# TGE_NEIL_v1.net
KiCad netlist of a schematic drawn in EAGLE
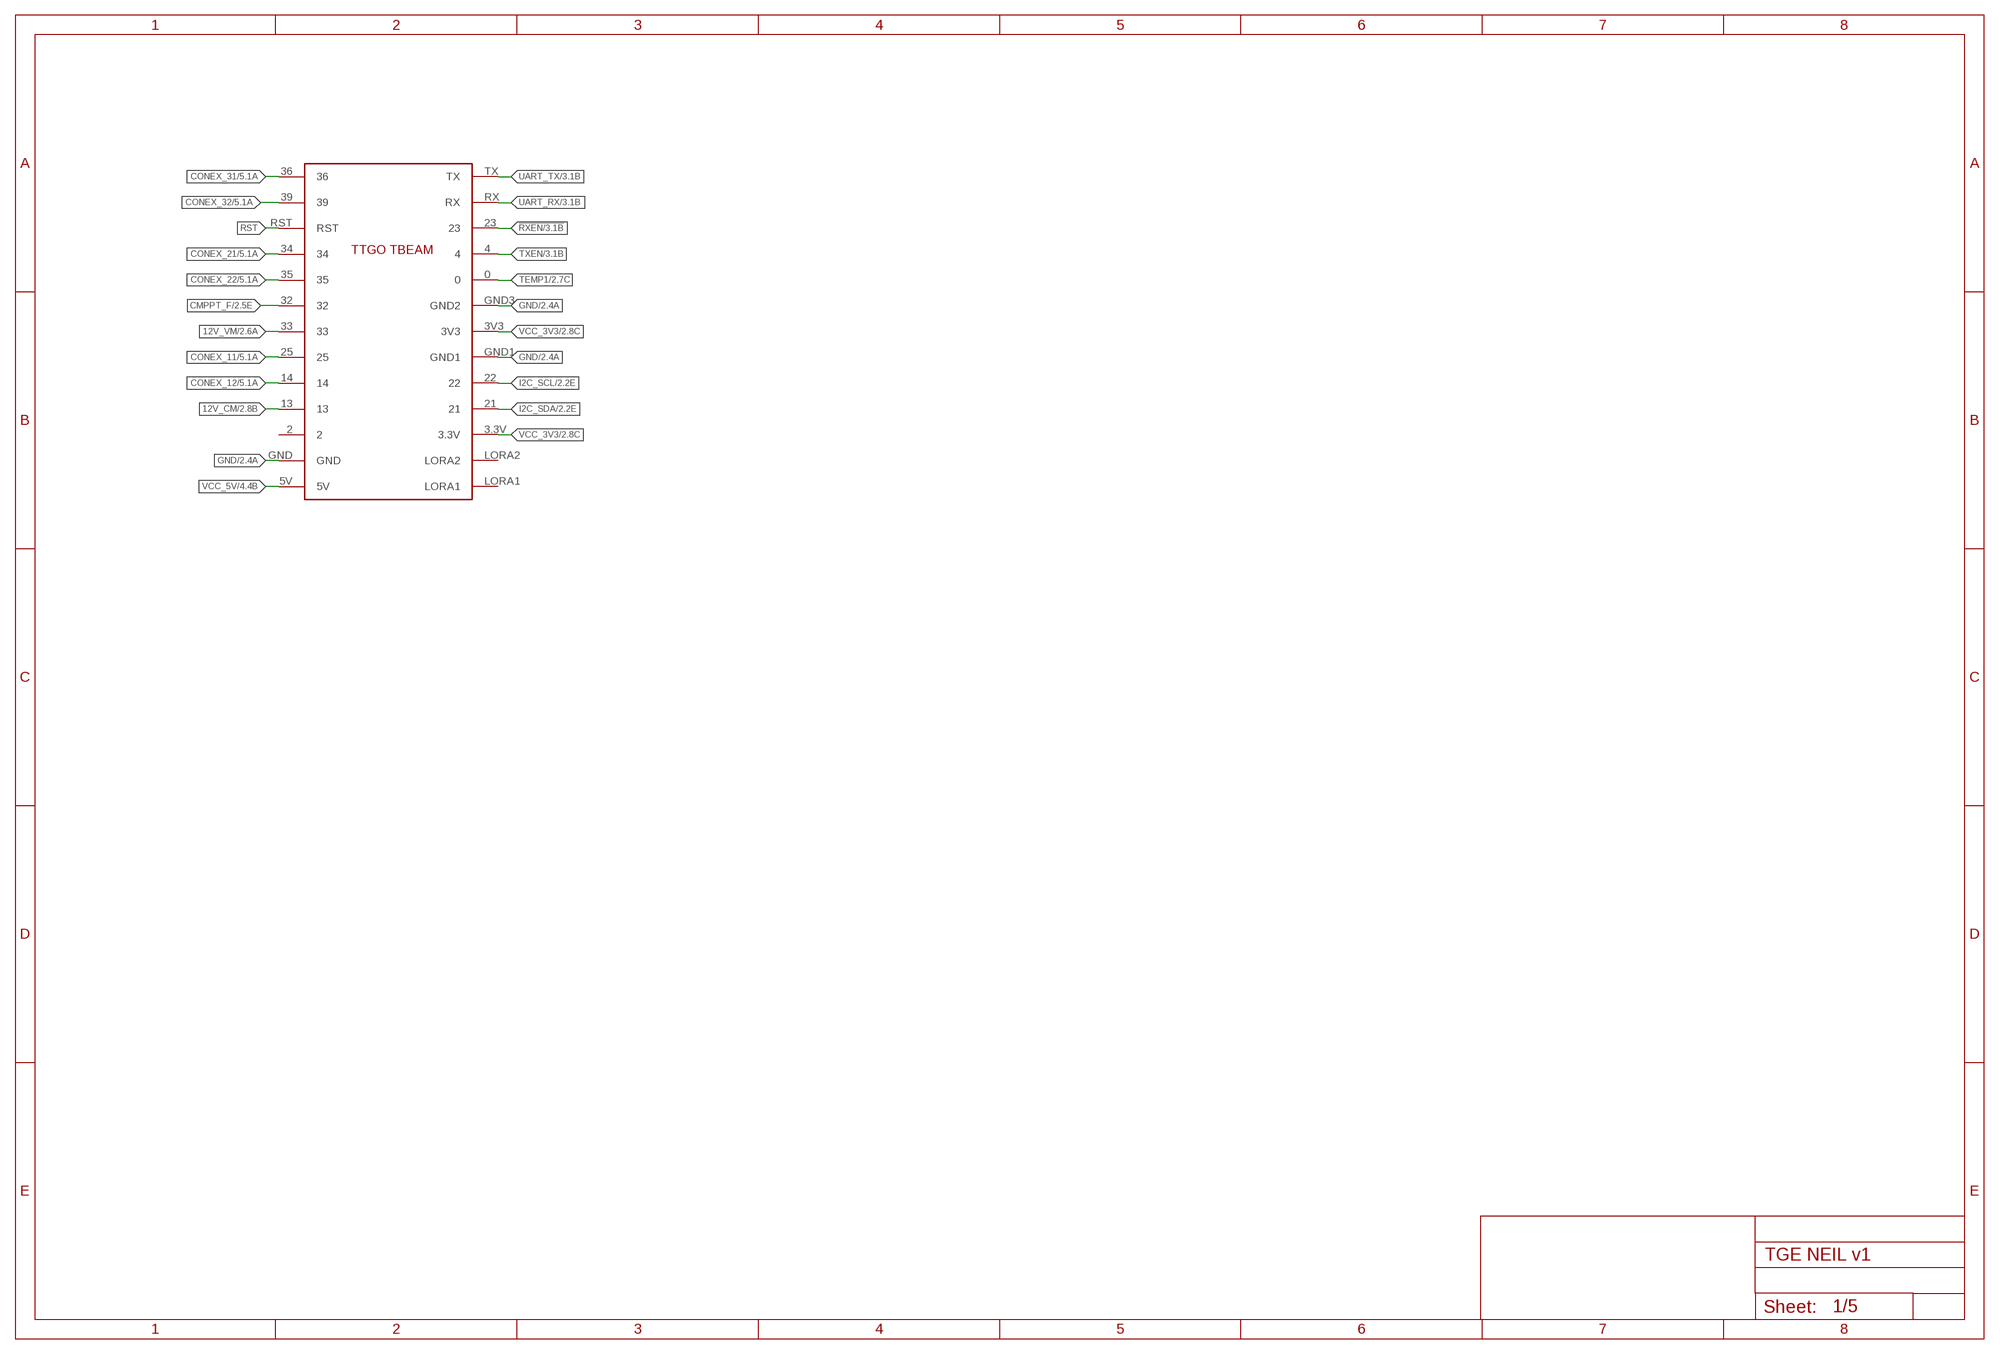
[diagram p0: schematic, sheet 1]
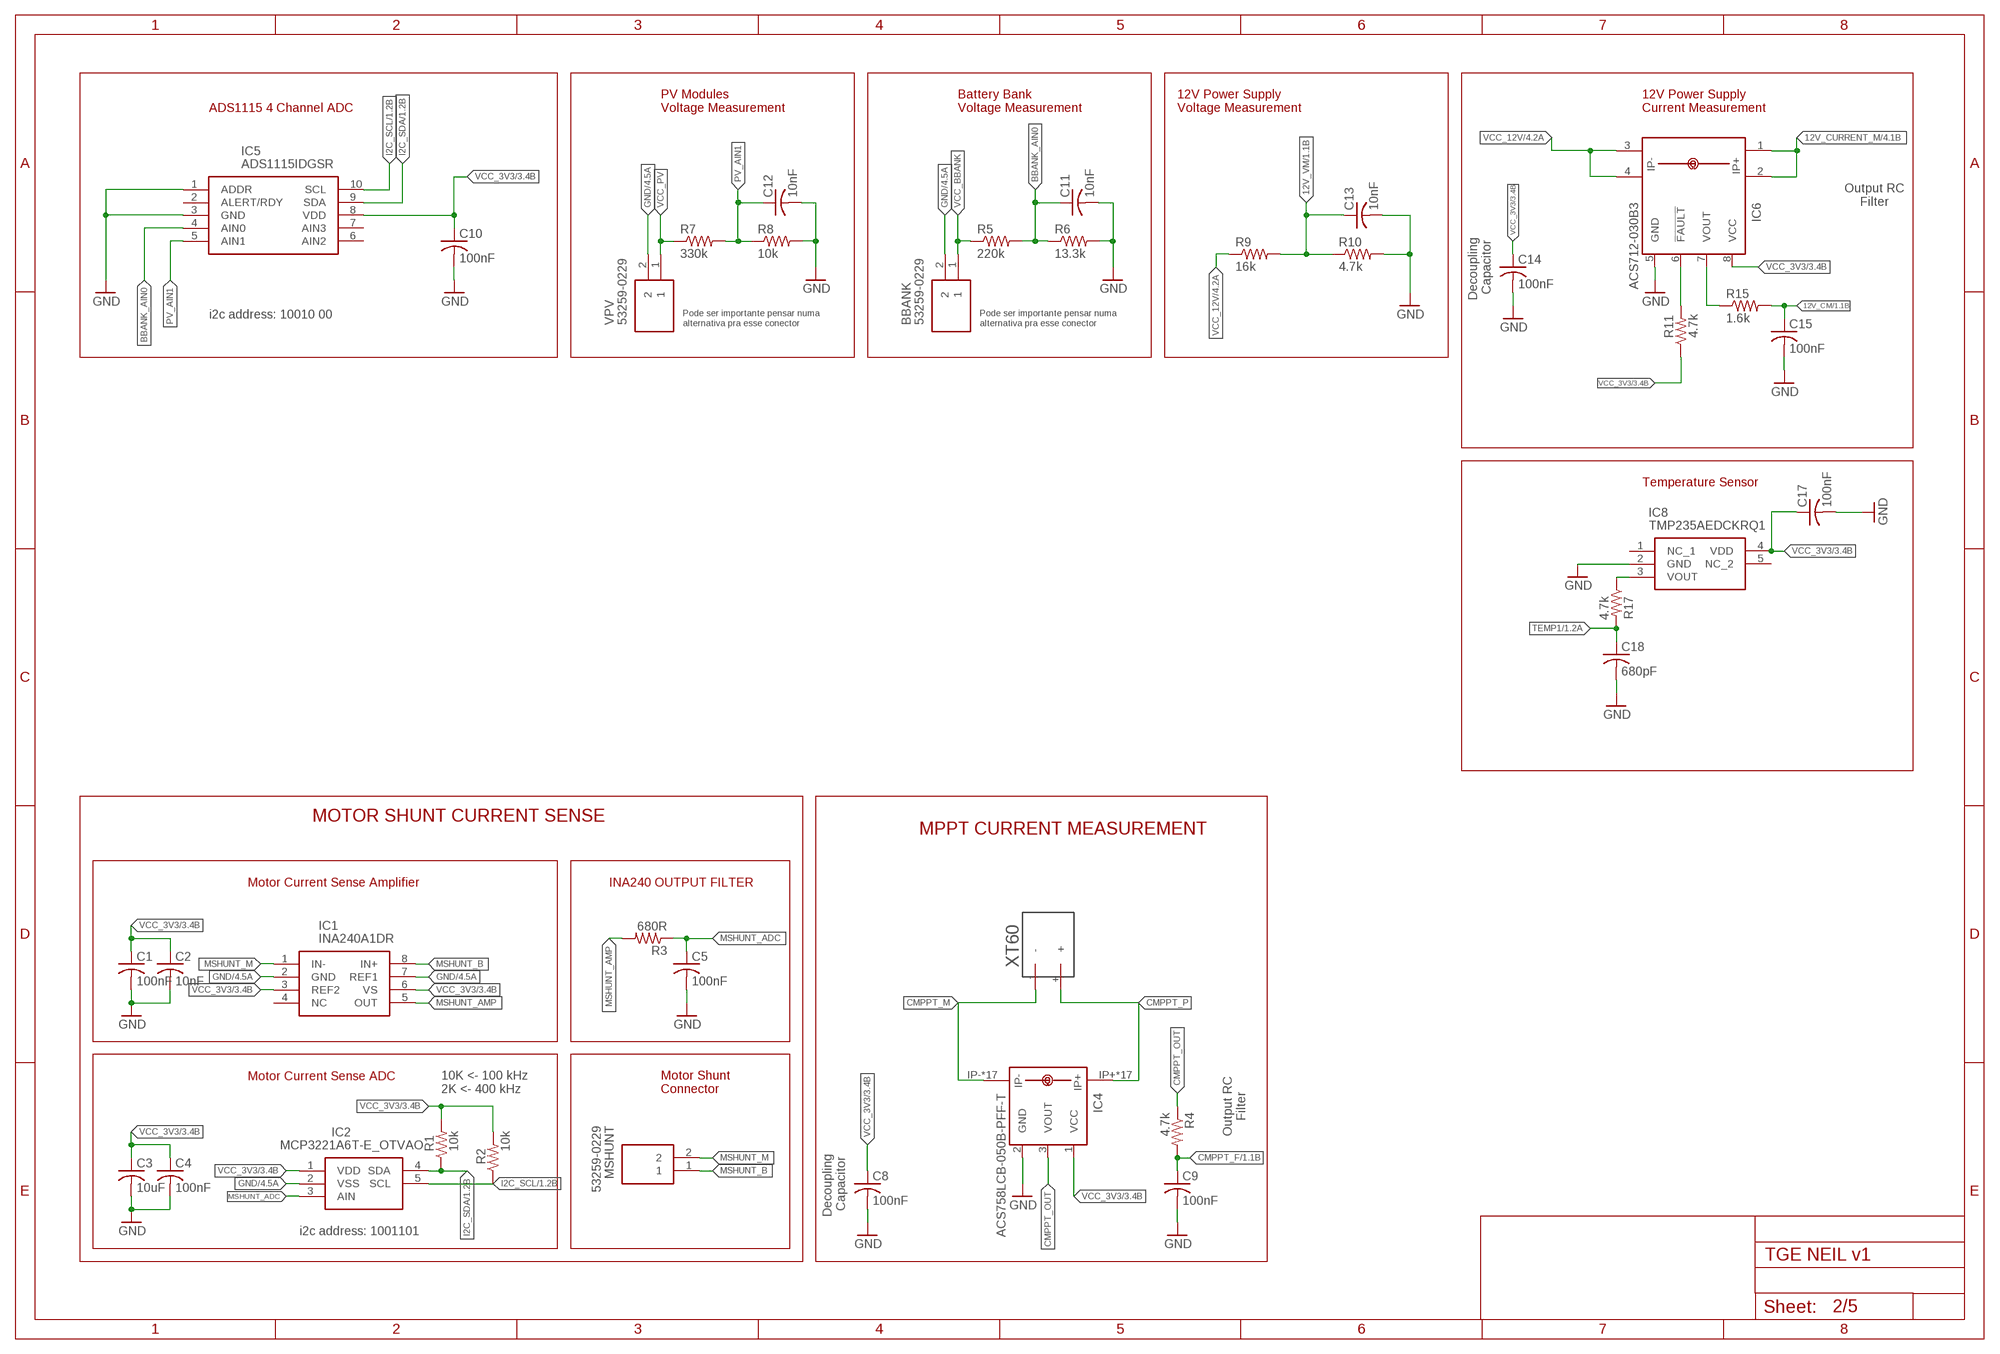
[diagram p1: schematic, sheet 2]
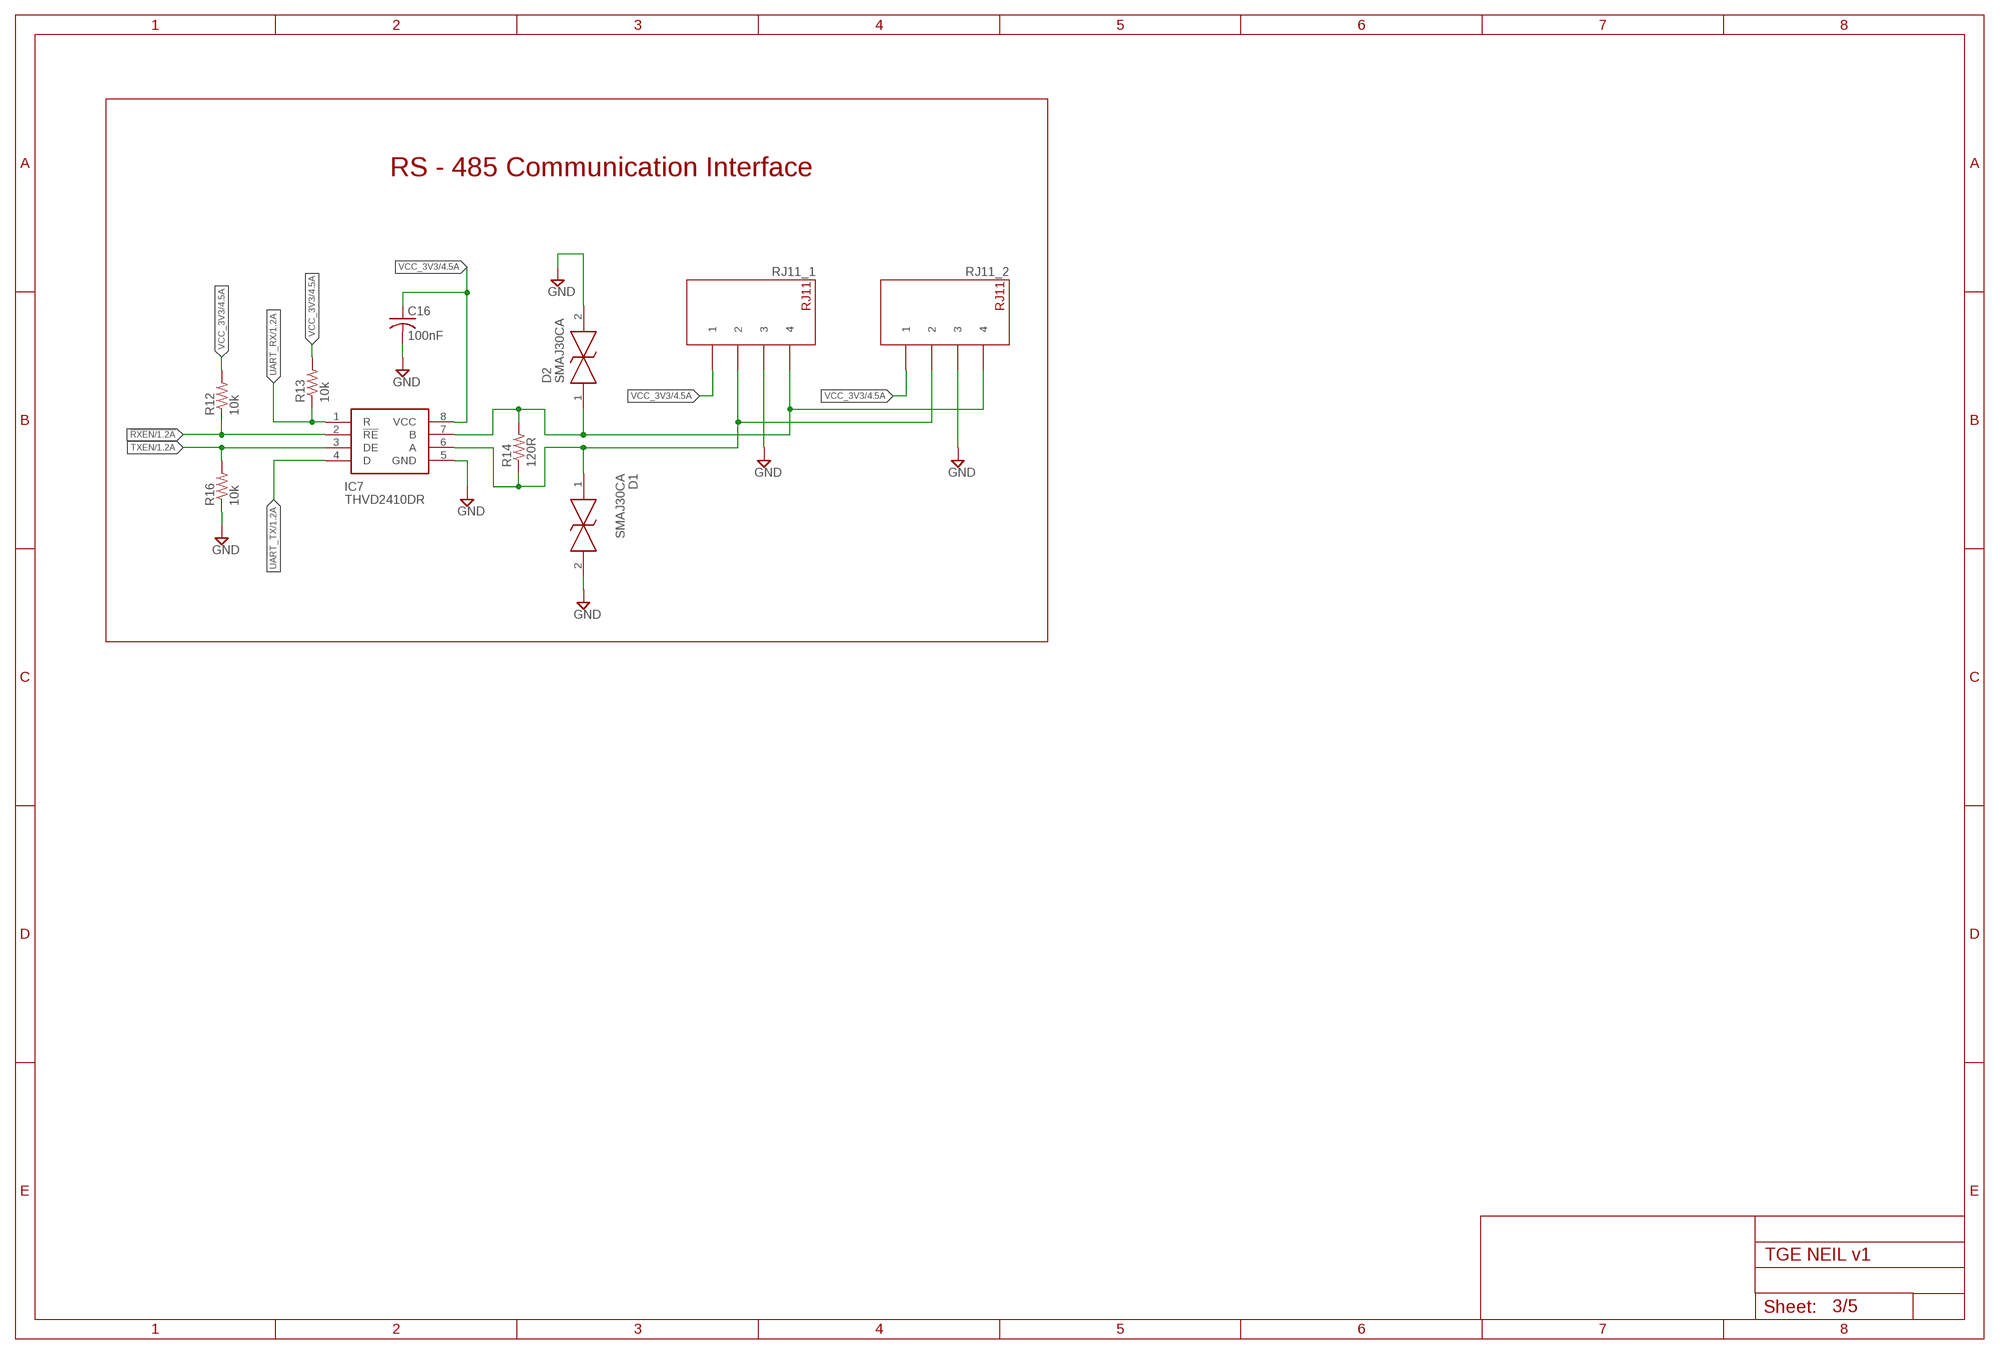
[diagram p2: schematic, sheet 3]
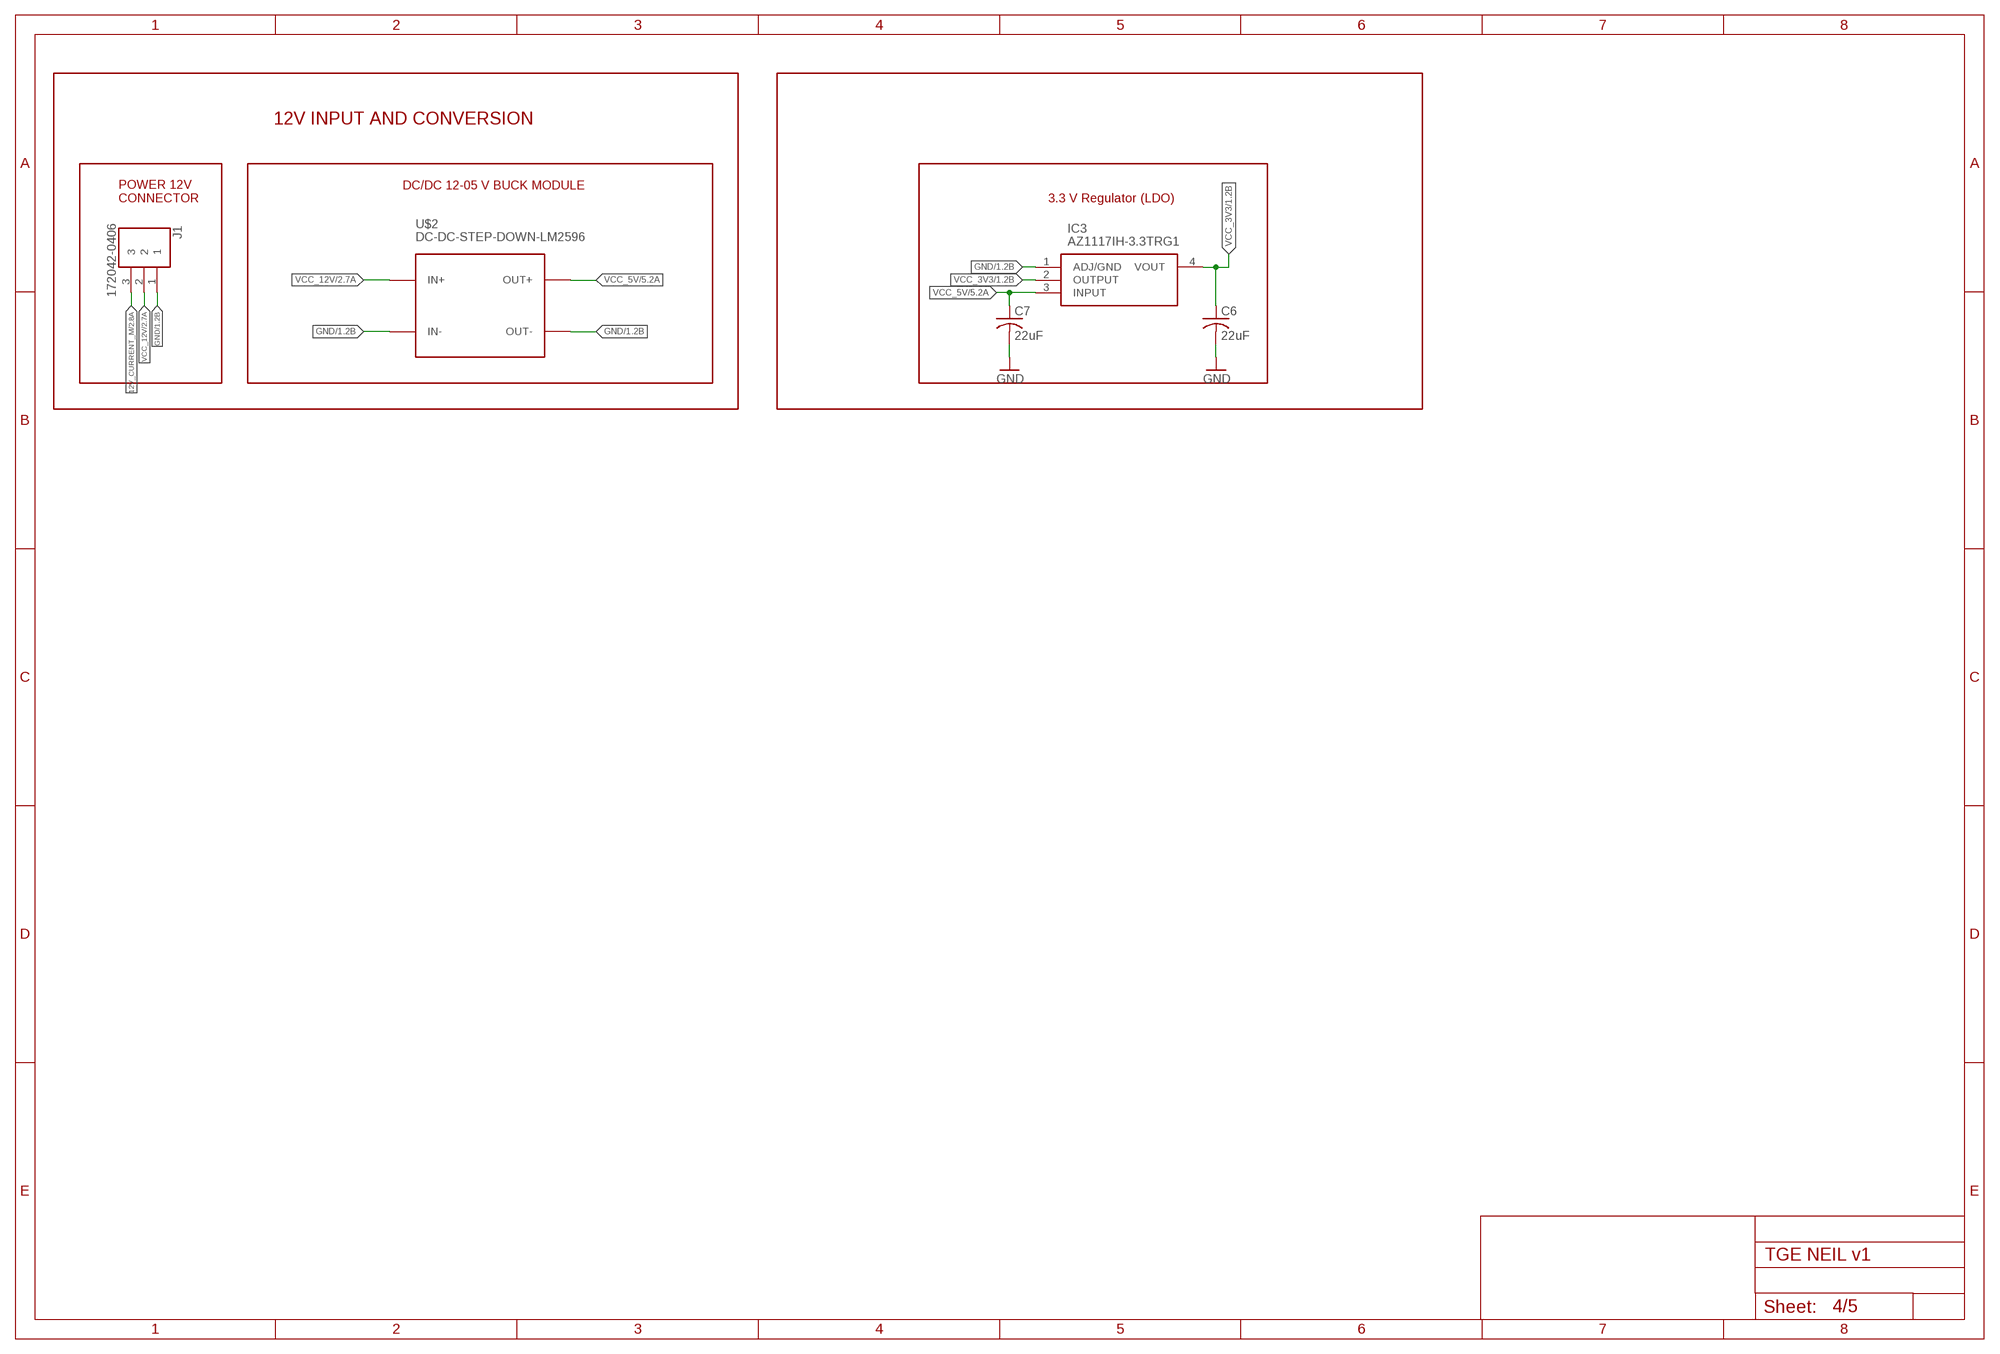
[diagram p3: schematic, sheet 4]
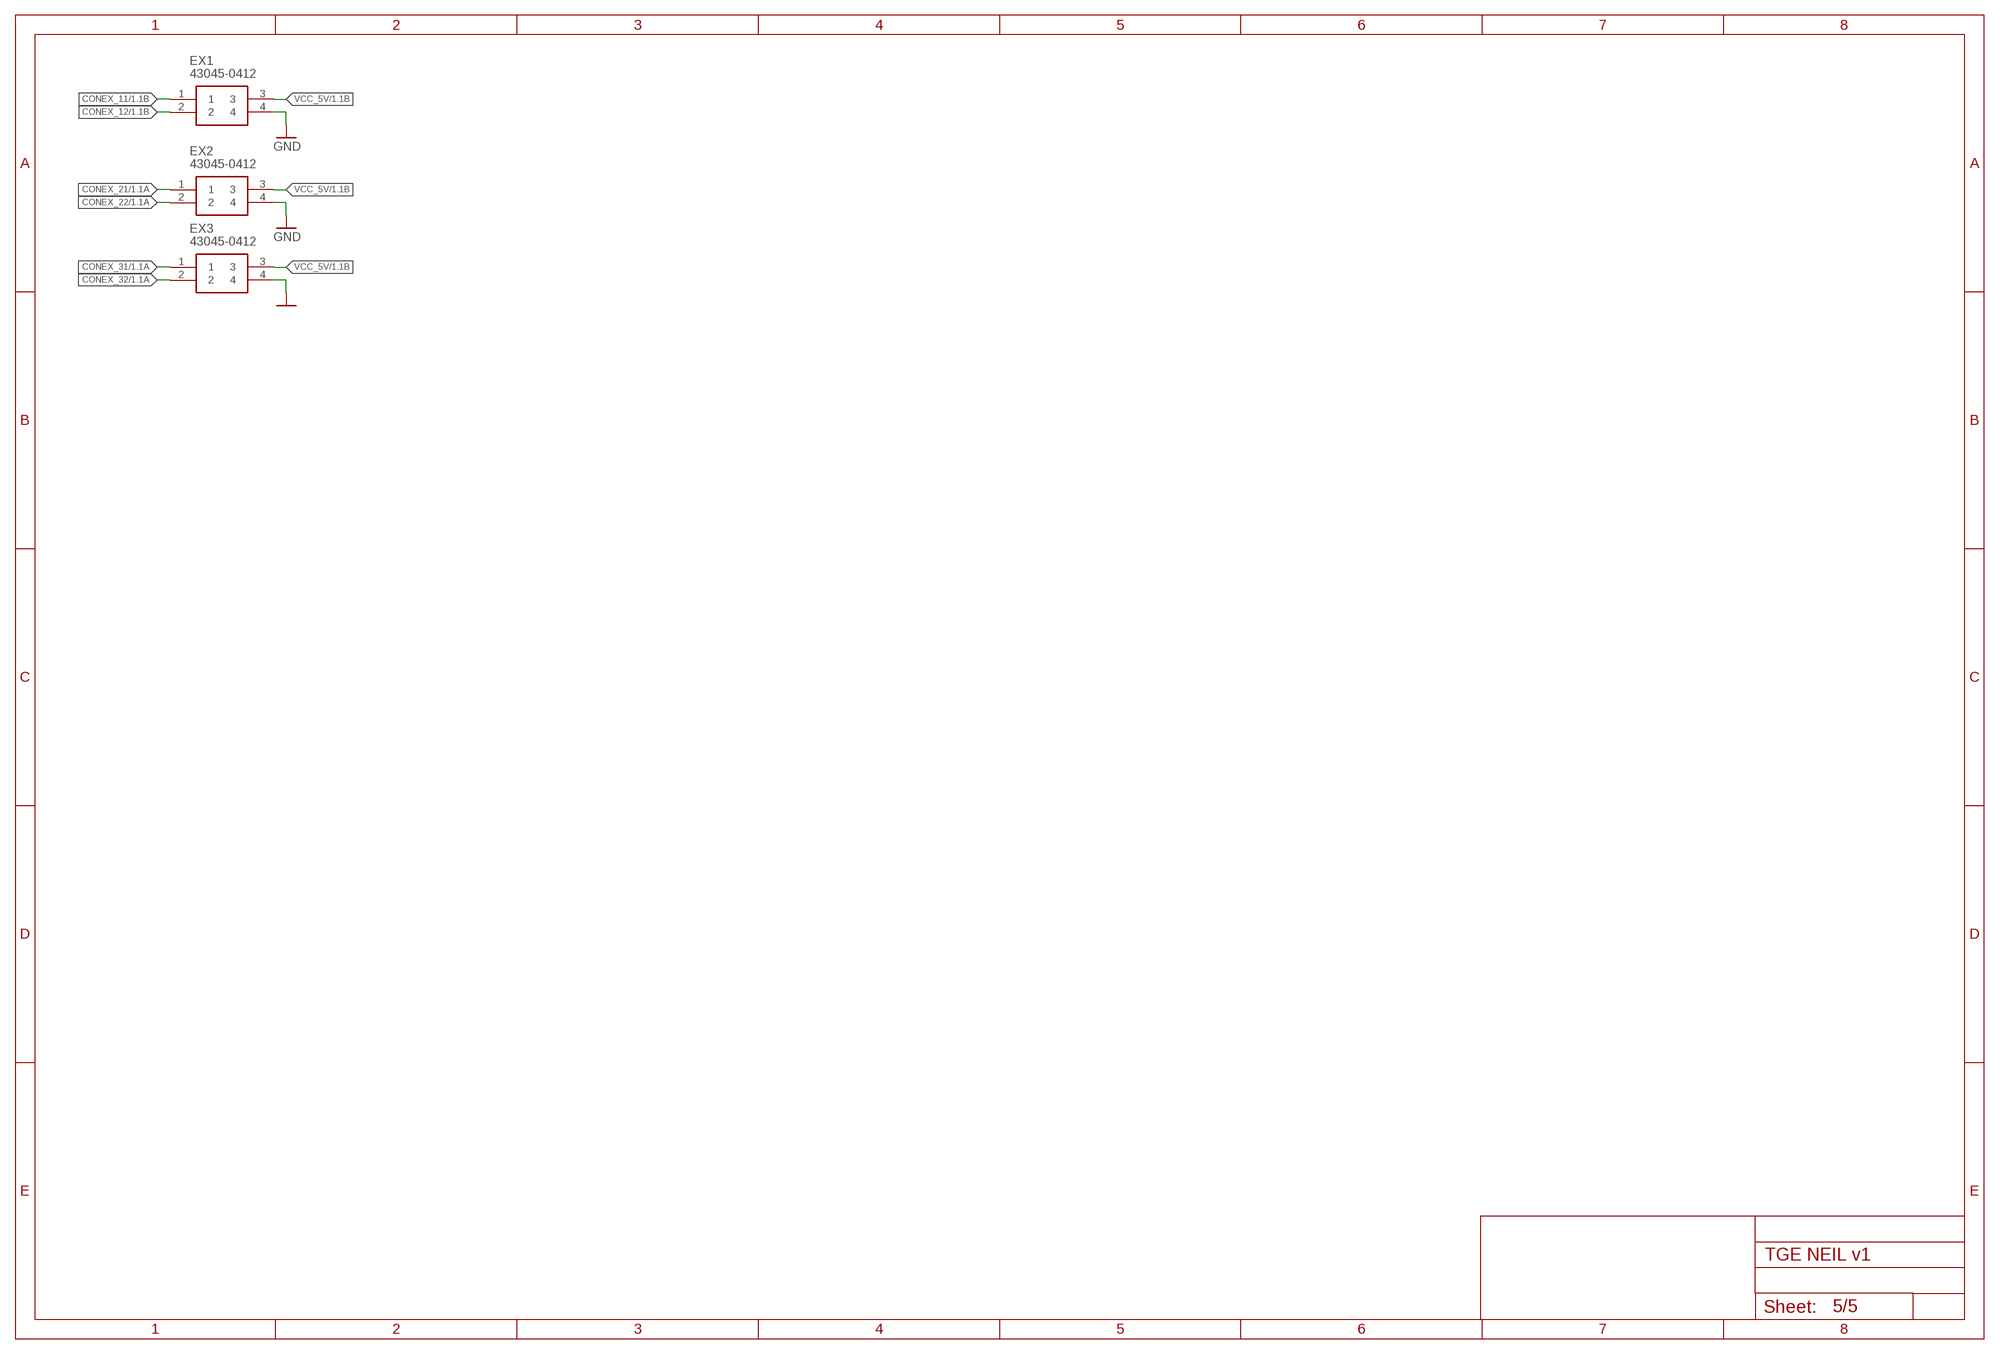
[diagram p4: schematic, sheet 5]

(export (version "E")
  (design (tool "Eeschema 10.0.6"))
  (components
    (comp (ref "BBANK")
      (value "53259-0229")
      (footprint "eagle-import:0532590229")
      (fields (field (name "MOUSER_PART_NUMBER") "538-53259-0229"))
      (libsource (lib "eagle-import") (part "53259-0229"))
    )
    (comp (ref "C1")
      (value "100nF")
      (footprint "eagle-import:C0805")
      (libsource (lib "eagle-import") (part "C-USC0805"))
    )
    (comp (ref "C2")
      (value "10nF")
      (footprint "eagle-import:C0805")
      (libsource (lib "eagle-import") (part "C-USC0805"))
    )
    (comp (ref "C3")
      (value "10uF")
      (footprint "eagle-import:C0805")
      (libsource (lib "eagle-import") (part "C-USC0805"))
    )
    (comp (ref "C4")
      (value "100nF")
      (footprint "eagle-import:C0805")
      (libsource (lib "eagle-import") (part "C-USC0805"))
    )
    (comp (ref "C5")
      (value "100nF")
      (footprint "eagle-import:C0805")
      (libsource (lib "eagle-import") (part "C-USC0805"))
    )
    (comp (ref "C8")
      (value "100nF")
      (footprint "eagle-import:C0805")
      (libsource (lib "eagle-import") (part "C-USC0805"))
    )
    (comp (ref "C9")
      (value "100nF")
      (footprint "eagle-import:C0805")
      (libsource (lib "eagle-import") (part "C-USC0805"))
    )
    (comp (ref "C10")
      (value "100nF")
      (footprint "eagle-import:C0805")
      (libsource (lib "eagle-import") (part "C-USC0805"))
    )
    (comp (ref "C11")
      (value "10nF")
      (footprint "eagle-import:C0805")
      (libsource (lib "eagle-import") (part "C-USC0805"))
    )
    (comp (ref "C12")
      (value "10nF")
      (footprint "eagle-import:C0805")
      (libsource (lib "eagle-import") (part "C-USC0805"))
    )
    (comp (ref "C13")
      (value "10nF")
      (footprint "eagle-import:C0805")
      (libsource (lib "eagle-import") (part "C-USC0805"))
    )
    (comp (ref "C14")
      (value "100nF")
      (footprint "eagle-import:C0805")
      (libsource (lib "eagle-import") (part "C-USC0805"))
    )
    (comp (ref "C15")
      (value "100nF")
      (footprint "eagle-import:C0805")
      (libsource (lib "eagle-import") (part "C-USC0805"))
    )
    (comp (ref "C17")
      (value "100nF")
      (footprint "eagle-import:C0805")
      (libsource (lib "eagle-import") (part "C-USC0805"))
    )
    (comp (ref "C18")
      (value "680pF")
      (footprint "eagle-import:C0805")
      (libsource (lib "eagle-import") (part "C-USC0805"))
    )
    (comp (ref "IC1")
      (value "INA240A1DR")
      (footprint "eagle-import:SOIC127P600X175-8N")
      (fields (field (name "MOUSER_PART_NUMBER") "595-INA240A1DR"))
      (libsource (lib "eagle-import") (part "INA240A1DR"))
    )
    (comp (ref "IC2")
      (value "MCP3221A6T-E_OTVAO")
      (footprint "eagle-import:SOT95P280X145-5N")
      (fields
        (field (name "MANUFACTURER_PART_NUMBER") "MCP3221A6T-E/OTVAO")
        (field (name "MOUSER_PART_NUMBER") "579-MCP3221A6TEOTVAO")
      )
      (libsource (lib "eagle-import") (part "MCP3221A6T-E_OTVAO"))
    )
    (comp (ref "IC4")
      (value "ACS758LCB-050B-PFF-T")
      (footprint "eagle-import:CB-PFF")
      (libsource (lib "eagle-import") (part "ACS758LCB-050B-PFF-T"))
    )
    (comp (ref "IC5")
      (value "ADS1115IDGSR")
      (footprint "eagle-import:SOP50P490X110-10N")
      (fields (field (name "MOUSER_PART_NUMBER") "595-ADS1115IDGSR"))
      (libsource (lib "eagle-import") (part "ADS1115IDGSR"))
    )
    (comp (ref "IC6")
      (value "ACS712-030B3")
      (footprint "eagle-import:SOIC8")
      (libsource (lib "eagle-import") (part "ACS712-LC"))
    )
    (comp (ref "IC8")
      (value "TMP235AEDCKRQ1")
      (footprint "eagle-import:SOT65P210X110-5N")
      (fields (field (name "MOUSER_PART_NUMBER") "595-TMP235AEDCKRQ1"))
      (libsource (lib "eagle-import") (part "TMP235AEDCKRQ1"))
    )
    (comp (ref "MSHUNT")
      (value "53259-0229")
      (footprint "eagle-import:0532590229")
      (fields (field (name "MOUSER_PART_NUMBER") "538-53259-0229"))
      (libsource (lib "eagle-import") (part "53259-0229"))
    )
    (comp (ref "R1")
      (value "10k")
      (footprint "eagle-import:R0805")
      (libsource (lib "eagle-import") (part "R-US_R0805"))
    )
    (comp (ref "R2")
      (value "10k")
      (footprint "eagle-import:R0805")
      (libsource (lib "eagle-import") (part "R-US_R0805"))
    )
    (comp (ref "R3")
      (value "680R")
      (footprint "eagle-import:R0805")
      (libsource (lib "eagle-import") (part "R-US_R0805"))
    )
    (comp (ref "R4")
      (value "4.7k")
      (footprint "eagle-import:R0805")
      (libsource (lib "eagle-import") (part "R-US_R0805"))
    )
    (comp (ref "R5")
      (value "220k")
      (footprint "eagle-import:R0805")
      (libsource (lib "eagle-import") (part "R-US_R0805"))
    )
    (comp (ref "R6")
      (value "13.3k")
      (footprint "eagle-import:R0805")
      (libsource (lib "eagle-import") (part "R-US_R0805"))
    )
    (comp (ref "R7")
      (value "330k")
      (footprint "eagle-import:R0805")
      (libsource (lib "eagle-import") (part "R-US_R0805"))
    )
    (comp (ref "R8")
      (value "10k")
      (footprint "eagle-import:R0805")
      (libsource (lib "eagle-import") (part "R-US_R0805"))
    )
    (comp (ref "R9")
      (value "16k")
      (footprint "eagle-import:R0805")
      (libsource (lib "eagle-import") (part "R-US_R0805"))
    )
    (comp (ref "R10")
      (value "4.7k")
      (footprint "eagle-import:R0805")
      (libsource (lib "eagle-import") (part "R-US_R0805"))
    )
    (comp (ref "R11")
      (value "4.7k")
      (footprint "eagle-import:R0805")
      (libsource (lib "eagle-import") (part "R-US_R0805"))
    )
    (comp (ref "R15")
      (value "1.6k")
      (footprint "eagle-import:R0805")
      (libsource (lib "eagle-import") (part "R-US_R0805"))
    )
    (comp (ref "R17")
      (value "4.7k")
      (footprint "eagle-import:R0805")
      (libsource (lib "eagle-import") (part "R-US_R0805"))
    )
    (comp (ref "U$3")
      (value "XT60")
      (footprint "eagle-import:XT60")
      (libsource (lib "eagle-import") (part "XT60"))
    )
    (comp (ref "VPV")
      (value "53259-0229")
      (footprint "eagle-import:0532590229")
      (fields (field (name "MOUSER_PART_NUMBER") "538-53259-0229"))
      (libsource (lib "eagle-import") (part "53259-0229"))
    )
    (comp (ref "EX1")
      (value "43045-0412")
      (footprint "eagle-import:43045-0412")
      (fields (field (name "MOUSER_PART_NUMBER") "538-43045-0412"))
      (libsource (lib "eagle-import") (part "43045-0412"))
    )
    (comp (ref "EX2")
      (value "43045-0412")
      (footprint "eagle-import:43045-0412")
      (fields (field (name "MOUSER_PART_NUMBER") "538-43045-0412"))
      (libsource (lib "eagle-import") (part "43045-0412"))
    )
    (comp (ref "EX3")
      (value "43045-0412")
      (footprint "eagle-import:43045-0412")
      (fields (field (name "MOUSER_PART_NUMBER") "538-43045-0412"))
      (libsource (lib "eagle-import") (part "43045-0412"))
    )
    (comp (ref "U$1")
      (value "TTGOBEAM")
      (footprint "eagle-import:TTGOBEAM")
      (libsource (lib "eagle-import") (part "TTGOBEAM"))
    )
    (comp (ref "C6")
      (value "22uF")
      (footprint "eagle-import:C0805")
      (libsource (lib "eagle-import") (part "C-USC0805"))
    )
    (comp (ref "C7")
      (value "22uF")
      (footprint "eagle-import:C0805")
      (libsource (lib "eagle-import") (part "C-USC0805"))
    )
    (comp (ref "IC3")
      (value "AZ1117IH-3.3TRG1")
      (footprint "eagle-import:SOT230P700X170-4N")
      (fields (field (name "MOUSER_PART_NUMBER") "621-AZ1117IH-3.3TRG1"))
      (libsource (lib "eagle-import") (part "AZ1117IH-3.3TRG1"))
    )
    (comp (ref "J1")
      (value "172042-0406")
      (footprint "eagle-import:MOLEX_172042-0406")
      (fields (field (name "MF") "Molex") (field (name "MP") "172042-0302"))
      (libsource (lib "eagle-import") (part "172042-0406"))
    )
    (comp (ref "U$2")
      (value "DC-DC-STEP-DOWN-LM2596")
      (footprint "eagle-import:DC-DC-STEP-DOWN-LM2596")
      (libsource (lib "eagle-import") (part "DC-DC-STEP-DOWN-LM2596"))
    )
    (comp (ref "C16")
      (value "100nF")
      (footprint "eagle-import:C0805")
      (libsource (lib "eagle-import") (part "C-USC0805"))
    )
    (comp (ref "D1")
      (value "SMAJ30CA")
      (footprint "eagle-import:DIONM5026X229N")
      (fields (field (name "MOUSER_PART_NUMBER") "576-SMAJ30CA"))
      (libsource (lib "eagle-import") (part "SMAJ30CA"))
    )
    (comp (ref "D2")
      (value "SMAJ30CA")
      (footprint "eagle-import:DIONM5026X229N")
      (fields (field (name "MOUSER_PART_NUMBER") "576-SMAJ30CA"))
      (libsource (lib "eagle-import") (part "SMAJ30CA"))
    )
    (comp (ref "IC7")
      (value "THVD2410DR")
      (footprint "eagle-import:SOIC127P600X175-8N")
      (fields (field (name "MOUSER_PART_NUMBER") "595-THVD2410DR"))
      (libsource (lib "eagle-import") (part "THVD2410DR"))
    )
    (comp (ref "R12")
      (value "10k")
      (footprint "eagle-import:M0805")
      (libsource (lib "eagle-import") (part "R-US_M0805"))
    )
    (comp (ref "R13")
      (value "10k")
      (footprint "eagle-import:M0805")
      (libsource (lib "eagle-import") (part "R-US_M0805"))
    )
    (comp (ref "R14")
      (value "120R")
      (footprint "eagle-import:M0805")
      (libsource (lib "eagle-import") (part "R-US_M0805"))
    )
    (comp (ref "R16")
      (value "10k")
      (footprint "eagle-import:M0805")
      (libsource (lib "eagle-import") (part "R-US_M0805"))
    )
    (comp (ref "RJ11_1")
      (value "TFC44")
      (footprint "eagle-import:TFC44")
      (libsource (lib "eagle-import") (part "TFC44"))
    )
    (comp (ref "RJ11_2")
      (value "TFC44")
      (footprint "eagle-import:TFC44")
      (libsource (lib "eagle-import") (part "TFC44"))
    )
  )
  (nets
    (net (code "1") (name "12V_CM") (class "Default")
      (node (ref "C15") (pin "1") (pinfunction "1_1") (pintype "passive"))
      (node (ref "R15") (pin "2") (pinfunction "2_2") (pintype "passive"))
      (node (ref "U$1") (pin "13") (pinfunction "13_13") (pintype "bidirectional"))
    )
    (net (code "2") (name "12V_CURRENT_M") (class "Default")
      (node (ref "IC6") (pin "1") (pinfunction "IP+_1") (pintype "passive"))
      (node (ref "IC6") (pin "2") (pinfunction "IP+1_2") (pintype "passive"))
      (node (ref "J1") (pin "3") (pinfunction "3_3") (pintype "passive"))
    )
    (net (code "3") (name "12V_VM") (class "Default")
      (node (ref "C13") (pin "1") (pinfunction "1_1") (pintype "passive"))
      (node (ref "R10") (pin "1") (pinfunction "1_1") (pintype "passive"))
      (node (ref "R9") (pin "2") (pinfunction "2_2") (pintype "passive"))
      (node (ref "U$1") (pin "33") (pinfunction "33_33") (pintype "bidirectional"))
    )
    (net (code "4") (name "BBANK_AIN0") (class "Default")
      (node (ref "C11") (pin "1") (pinfunction "1_1") (pintype "passive"))
      (node (ref "IC5") (pin "4") (pinfunction "AIN0_4") (pintype "bidirectional"))
      (node (ref "R5") (pin "2") (pinfunction "2_2") (pintype "passive"))
      (node (ref "R6") (pin "1") (pinfunction "1_1") (pintype "passive"))
    )
    (net (code "5") (name "CMPPT_F") (class "Default")
      (node (ref "C9") (pin "1") (pinfunction "1_1") (pintype "passive"))
      (node (ref "R4") (pin "2") (pinfunction "2_2") (pintype "passive"))
      (node (ref "U$1") (pin "32") (pinfunction "32_32") (pintype "bidirectional"))
    )
    (net (code "6") (name "CMPPT_M") (class "Default")
      (node (ref "IC4") (pin "IP-") (pinfunction "IP-_IP-") (pintype "passive"))
      (node (ref "IC4") (pin "IP-@10") (pinfunction "IP-_IP-@10") (pintype "passive"))
      (node (ref "IC4") (pin "IP-@11") (pinfunction "IP-_IP-@11") (pintype "passive"))
      (node (ref "IC4") (pin "IP-@12") (pinfunction "IP-_IP-@12") (pintype "passive"))
      (node (ref "IC4") (pin "IP-@13") (pinfunction "IP-_IP-@13") (pintype "passive"))
      (node (ref "IC4") (pin "IP-@14") (pinfunction "IP-_IP-@14") (pintype "passive"))
      (node (ref "IC4") (pin "IP-@15") (pinfunction "IP-_IP-@15") (pintype "passive"))
      (node (ref "IC4") (pin "IP-@16") (pinfunction "IP-_IP-@16") (pintype "passive"))
      (node (ref "IC4") (pin "IP-@17") (pinfunction "IP-_IP-@17") (pintype "passive"))
      (node (ref "IC4") (pin "IP-@2") (pinfunction "IP-_IP-@2") (pintype "passive"))
      (node (ref "IC4") (pin "IP-@3") (pinfunction "IP-_IP-@3") (pintype "passive"))
      (node (ref "IC4") (pin "IP-@4") (pinfunction "IP-_IP-@4") (pintype "passive"))
      (node (ref "IC4") (pin "IP-@5") (pinfunction "IP-_IP-@5") (pintype "passive"))
      (node (ref "IC4") (pin "IP-@6") (pinfunction "IP-_IP-@6") (pintype "passive"))
      (node (ref "IC4") (pin "IP-@7") (pinfunction "IP-_IP-@7") (pintype "passive"))
      (node (ref "IC4") (pin "IP-@8") (pinfunction "IP-_IP-@8") (pintype "passive"))
      (node (ref "IC4") (pin "IP-@9") (pinfunction "IP-_IP-@9") (pintype "passive"))
      (node (ref "U$3") (pin "-") (pinfunction "-_-") (pintype "bidirectional"))
    )
    (net (code "7") (name "CMPPT_OUT") (class "Default")
      (node (ref "IC4") (pin "3") (pinfunction "VOUT_3") (pintype "output"))
      (node (ref "R4") (pin "1") (pinfunction "1_1") (pintype "passive"))
    )
    (net (code "8") (name "CMPPT_P") (class "Default")
      (node (ref "IC4") (pin "IP+") (pinfunction "IP+_IP+") (pintype "passive"))
      (node (ref "IC4") (pin "IP+@10") (pinfunction "IP+_IP+@10") (pintype "passive"))
      (node (ref "IC4") (pin "IP+@11") (pinfunction "IP+_IP+@11") (pintype "passive"))
      (node (ref "IC4") (pin "IP+@12") (pinfunction "IP+_IP+@12") (pintype "passive"))
      (node (ref "IC4") (pin "IP+@13") (pinfunction "IP+_IP+@13") (pintype "passive"))
      (node (ref "IC4") (pin "IP+@14") (pinfunction "IP+_IP+@14") (pintype "passive"))
      (node (ref "IC4") (pin "IP+@15") (pinfunction "IP+_IP+@15") (pintype "passive"))
      (node (ref "IC4") (pin "IP+@16") (pinfunction "IP+_IP+@16") (pintype "passive"))
      (node (ref "IC4") (pin "IP+@17") (pinfunction "IP+_IP+@17") (pintype "passive"))
      (node (ref "IC4") (pin "IP+@2") (pinfunction "IP+_IP+@2") (pintype "passive"))
      (node (ref "IC4") (pin "IP+@3") (pinfunction "IP+_IP+@3") (pintype "passive"))
      (node (ref "IC4") (pin "IP+@4") (pinfunction "IP+_IP+@4") (pintype "passive"))
      (node (ref "IC4") (pin "IP+@5") (pinfunction "IP+_IP+@5") (pintype "passive"))
      (node (ref "IC4") (pin "IP+@6") (pinfunction "IP+_IP+@6") (pintype "passive"))
      (node (ref "IC4") (pin "IP+@7") (pinfunction "IP+_IP+@7") (pintype "passive"))
      (node (ref "IC4") (pin "IP+@8") (pinfunction "IP+_IP+@8") (pintype "passive"))
      (node (ref "IC4") (pin "IP+@9") (pinfunction "IP+_IP+@9") (pintype "passive"))
      (node (ref "U$3") (pin "+") (pinfunction "+_+") (pintype "bidirectional"))
    )
    (net (code "9") (name "CONEX_11") (class "Default")
      (node (ref "EX1") (pin "1") (pinfunction "1_1") (pintype "bidirectional"))
      (node (ref "U$1") (pin "25") (pinfunction "25_25") (pintype "bidirectional"))
    )
    (net (code "10") (name "CONEX_12") (class "Default")
      (node (ref "EX1") (pin "2") (pinfunction "2_2") (pintype "bidirectional"))
      (node (ref "U$1") (pin "14") (pinfunction "14_14") (pintype "bidirectional"))
    )
    (net (code "11") (name "CONEX_21") (class "Default")
      (node (ref "EX2") (pin "1") (pinfunction "1_1") (pintype "bidirectional"))
      (node (ref "U$1") (pin "34") (pinfunction "34_34") (pintype "bidirectional"))
    )
    (net (code "12") (name "CONEX_22") (class "Default")
      (node (ref "EX2") (pin "2") (pinfunction "2_2") (pintype "bidirectional"))
      (node (ref "U$1") (pin "35") (pinfunction "35_35") (pintype "bidirectional"))
    )
    (net (code "13") (name "CONEX_31") (class "Default")
      (node (ref "EX3") (pin "1") (pinfunction "1_1") (pintype "bidirectional"))
      (node (ref "U$1") (pin "36") (pinfunction "36_36") (pintype "bidirectional"))
    )
    (net (code "14") (name "CONEX_32") (class "Default")
      (node (ref "EX3") (pin "2") (pinfunction "2_2") (pintype "bidirectional"))
      (node (ref "U$1") (pin "39") (pinfunction "39_39") (pintype "bidirectional"))
    )
    (net (code "15") (name "GND") (class "Default")
      (node (ref "BBANK") (pin "2") (pinfunction "2_2") (pintype "bidirectional"))
      (node (ref "C1") (pin "2") (pinfunction "2_2") (pintype "passive"))
      (node (ref "C10") (pin "2") (pinfunction "2_2") (pintype "passive"))
      (node (ref "C11") (pin "2") (pinfunction "2_2") (pintype "passive"))
      (node (ref "C12") (pin "2") (pinfunction "2_2") (pintype "passive"))
      (node (ref "C13") (pin "2") (pinfunction "2_2") (pintype "passive"))
      (node (ref "C14") (pin "2") (pinfunction "2_2") (pintype "passive"))
      (node (ref "C15") (pin "2") (pinfunction "2_2") (pintype "passive"))
      (node (ref "C16") (pin "2") (pinfunction "2_2") (pintype "passive"))
      (node (ref "C17") (pin "2") (pinfunction "2_2") (pintype "passive"))
      (node (ref "C18") (pin "2") (pinfunction "2_2") (pintype "passive"))
      (node (ref "C2") (pin "2") (pinfunction "2_2") (pintype "passive"))
      (node (ref "C3") (pin "2") (pinfunction "2_2") (pintype "passive"))
      (node (ref "C4") (pin "2") (pinfunction "2_2") (pintype "passive"))
      (node (ref "C5") (pin "2") (pinfunction "2_2") (pintype "passive"))
      (node (ref "C6") (pin "2") (pinfunction "2_2") (pintype "passive"))
      (node (ref "C7") (pin "2") (pinfunction "2_2") (pintype "passive"))
      (node (ref "C8") (pin "2") (pinfunction "2_2") (pintype "passive"))
      (node (ref "C9") (pin "2") (pinfunction "2_2") (pintype "passive"))
      (node (ref "D1") (pin "2") (pinfunction "2_2") (pintype "bidirectional"))
      (node (ref "D2") (pin "2") (pinfunction "2_2") (pintype "bidirectional"))
      (node (ref "EX1") (pin "4") (pinfunction "4_4") (pintype "bidirectional"))
      (node (ref "EX2") (pin "4") (pinfunction "4_4") (pintype "bidirectional"))
      (node (ref "EX3") (pin "4") (pinfunction "4_4") (pintype "bidirectional"))
      (node (ref "IC1") (pin "2") (pinfunction "GND_2") (pintype "bidirectional"))
      (node (ref "IC1") (pin "7") (pinfunction "REF1_7") (pintype "bidirectional"))
      (node (ref "IC2") (pin "2") (pinfunction "VSS_2") (pintype "bidirectional"))
      (node (ref "IC3") (pin "1") (pinfunction "ADJ/GND_1") (pintype "bidirectional"))
      (node (ref "IC4") (pin "2") (pinfunction "GND_2") (pintype "power_in"))
      (node (ref "IC5") (pin "1") (pinfunction "ADDR_1") (pintype "bidirectional"))
      (node (ref "IC5") (pin "3") (pinfunction "GND_3") (pintype "bidirectional"))
      (node (ref "IC6") (pin "5") (pinfunction "GND_5") (pintype "power_in"))
      (node (ref "IC7") (pin "5") (pinfunction "GND_5") (pintype "bidirectional"))
      (node (ref "IC8") (pin "2") (pinfunction "GND_2") (pintype "bidirectional"))
      (node (ref "J1") (pin "1") (pinfunction "1_1") (pintype "passive"))
      (node (ref "R10") (pin "2") (pinfunction "2_2") (pintype "passive"))
      (node (ref "R16") (pin "1") (pinfunction "1_1") (pintype "passive"))
      (node (ref "R6") (pin "2") (pinfunction "2_2") (pintype "passive"))
      (node (ref "R8") (pin "2") (pinfunction "2_2") (pintype "passive"))
      (node (ref "RJ11_1") (pin "P$3") (pinfunction "3_P$3") (pintype "bidirectional"))
      (node (ref "RJ11_2") (pin "P$3") (pinfunction "3_P$3") (pintype "bidirectional"))
      (node (ref "U$1") (pin "GND") (pinfunction "GND_GND") (pintype "bidirectional"))
      (node (ref "U$1") (pin "GND1") (pinfunction "GND1_GND1") (pintype "bidirectional"))
      (node (ref "U$1") (pin "GND3") (pinfunction "GND2_GND3") (pintype "bidirectional"))
      (node (ref "U$2") (pin "IN-") (pinfunction "IN-_IN-") (pintype "bidirectional"))
      (node (ref "U$2") (pin "OUT-") (pinfunction "OUT-_OUT-") (pintype "bidirectional"))
      (node (ref "VPV") (pin "2") (pinfunction "2_2") (pintype "bidirectional"))
    )
    (net (code "16") (name "I2C_SCL") (class "Default")
      (node (ref "IC2") (pin "5") (pinfunction "SCL_5") (pintype "bidirectional"))
      (node (ref "IC5") (pin "10") (pinfunction "SCL_10") (pintype "bidirectional"))
      (node (ref "R2") (pin "1") (pinfunction "1_1") (pintype "passive"))
      (node (ref "U$1") (pin "22") (pinfunction "22_22") (pintype "bidirectional"))
    )
    (net (code "17") (name "I2C_SDA") (class "Default")
      (node (ref "IC2") (pin "4") (pinfunction "SDA_4") (pintype "bidirectional"))
      (node (ref "IC5") (pin "9") (pinfunction "SDA_9") (pintype "bidirectional"))
      (node (ref "R1") (pin "1") (pinfunction "1_1") (pintype "passive"))
      (node (ref "U$1") (pin "21") (pinfunction "21_21") (pintype "bidirectional"))
    )
    (net (code "18") (name "MSHUNT_ADC") (class "Default")
      (node (ref "C5") (pin "1") (pinfunction "1_1") (pintype "passive"))
      (node (ref "IC2") (pin "3") (pinfunction "AIN_3") (pintype "bidirectional"))
      (node (ref "R3") (pin "1") (pinfunction "1_1") (pintype "passive"))
    )
    (net (code "19") (name "MSHUNT_AMP") (class "Default")
      (node (ref "IC1") (pin "5") (pinfunction "OUT_5") (pintype "bidirectional"))
      (node (ref "R3") (pin "2") (pinfunction "2_2") (pintype "passive"))
    )
    (net (code "20") (name "MSHUNT_B") (class "Default")
      (node (ref "IC1") (pin "8") (pinfunction "IN+_8") (pintype "bidirectional"))
      (node (ref "MSHUNT") (pin "1") (pinfunction "1_1") (pintype "bidirectional"))
    )
    (net (code "21") (name "MSHUNT_M") (class "Default")
      (node (ref "IC1") (pin "1") (pinfunction "IN-_1") (pintype "bidirectional"))
      (node (ref "MSHUNT") (pin "2") (pinfunction "2_2") (pintype "bidirectional"))
    )
    (net (code "22") (name "Net-(IC6-VOUT)") (class "Default")
      (node (ref "IC6") (pin "7") (pinfunction "VOUT_7") (pintype "output"))
      (node (ref "R15") (pin "1") (pinfunction "1_1") (pintype "passive"))
    )
    (net (code "23") (name "Net-(IC6-~{FAULT})") (class "Default")
      (node (ref "IC6") (pin "6") (pinfunction "~{FAULT}_6") (pintype "bidirectional"))
      (node (ref "R11") (pin "2") (pinfunction "2_2") (pintype "passive"))
    )
    (net (code "24") (name "Net-(IC7-A)") (class "Default")
      (node (ref "D1") (pin "1") (pinfunction "1_1") (pintype "bidirectional"))
      (node (ref "IC7") (pin "6") (pinfunction "A_6") (pintype "bidirectional"))
      (node (ref "R14") (pin "1") (pinfunction "1_1") (pintype "passive"))
      (node (ref "RJ11_1") (pin "P$2") (pinfunction "2_P$2") (pintype "bidirectional"))
      (node (ref "RJ11_2") (pin "P$2") (pinfunction "2_P$2") (pintype "bidirectional"))
    )
    (net (code "25") (name "Net-(IC7-B)") (class "Default")
      (node (ref "D2") (pin "1") (pinfunction "1_1") (pintype "bidirectional"))
      (node (ref "IC7") (pin "7") (pinfunction "B_7") (pintype "bidirectional"))
      (node (ref "R14") (pin "2") (pinfunction "2_2") (pintype "passive"))
      (node (ref "RJ11_1") (pin "P$4") (pinfunction "4_P$4") (pintype "bidirectional"))
      (node (ref "RJ11_2") (pin "P$4") (pinfunction "4_P$4") (pintype "bidirectional"))
    )
    (net (code "26") (name "Net-(IC8-VOUT)") (class "Default")
      (node (ref "IC8") (pin "3") (pinfunction "VOUT_3") (pintype "bidirectional"))
      (node (ref "R17") (pin "1") (pinfunction "1_1") (pintype "passive"))
    )
    (net (code "27") (name "PV_AIN1") (class "Default")
      (node (ref "C12") (pin "1") (pinfunction "1_1") (pintype "passive"))
      (node (ref "IC5") (pin "5") (pinfunction "AIN1_5") (pintype "bidirectional"))
      (node (ref "R7") (pin "2") (pinfunction "2_2") (pintype "passive"))
      (node (ref "R8") (pin "1") (pinfunction "1_1") (pintype "passive"))
    )
    (net (code "28") (name "RST") (class "Default")
      (node (ref "U$1") (pin "RST") (pinfunction "RST_RST") (pintype "bidirectional"))
    )
    (net (code "29") (name "TEMP1") (class "Default")
      (node (ref "C18") (pin "1") (pinfunction "1_1") (pintype "passive"))
      (node (ref "R17") (pin "2") (pinfunction "2_2") (pintype "passive"))
      (node (ref "U$1") (pin "0") (pinfunction "0_0") (pintype "bidirectional"))
    )
    (net (code "30") (name "TXEN") (class "Default")
      (node (ref "IC7") (pin "3") (pinfunction "DE_3") (pintype "bidirectional"))
      (node (ref "R16") (pin "2") (pinfunction "2_2") (pintype "passive"))
      (node (ref "U$1") (pin "4") (pinfunction "4_4") (pintype "bidirectional"))
    )
    (net (code "31") (name "UART_RX") (class "Default")
      (node (ref "IC7") (pin "1") (pinfunction "R_1") (pintype "bidirectional"))
      (node (ref "R13") (pin "1") (pinfunction "1_1") (pintype "passive"))
      (node (ref "U$1") (pin "RX") (pinfunction "RX_RX") (pintype "bidirectional"))
    )
    (net (code "32") (name "UART_TX") (class "Default")
      (node (ref "IC7") (pin "4") (pinfunction "D_4") (pintype "bidirectional"))
      (node (ref "U$1") (pin "TX") (pinfunction "TX_TX") (pintype "bidirectional"))
    )
    (net (code "33") (name "VCC_3V3") (class "Default")
      (node (ref "C1") (pin "1") (pinfunction "1_1") (pintype "passive"))
      (node (ref "C10") (pin "1") (pinfunction "1_1") (pintype "passive"))
      (node (ref "C14") (pin "1") (pinfunction "1_1") (pintype "passive"))
      (node (ref "C16") (pin "1") (pinfunction "1_1") (pintype "passive"))
      (node (ref "C17") (pin "1") (pinfunction "1_1") (pintype "passive"))
      (node (ref "C2") (pin "1") (pinfunction "1_1") (pintype "passive"))
      (node (ref "C3") (pin "1") (pinfunction "1_1") (pintype "passive"))
      (node (ref "C4") (pin "1") (pinfunction "1_1") (pintype "passive"))
      (node (ref "C6") (pin "1") (pinfunction "1_1") (pintype "passive"))
      (node (ref "C8") (pin "1") (pinfunction "1_1") (pintype "passive"))
      (node (ref "IC1") (pin "3") (pinfunction "REF2_3") (pintype "bidirectional"))
      (node (ref "IC1") (pin "6") (pinfunction "VS_6") (pintype "bidirectional"))
      (node (ref "IC2") (pin "1") (pinfunction "VDD_1") (pintype "bidirectional"))
      (node (ref "IC3") (pin "2") (pinfunction "OUTPUT_2") (pintype "bidirectional"))
      (node (ref "IC3") (pin "4") (pinfunction "VOUT_4") (pintype "bidirectional"))
      (node (ref "IC4") (pin "1") (pinfunction "VCC_1") (pintype "power_in"))
      (node (ref "IC5") (pin "8") (pinfunction "VDD_8") (pintype "bidirectional"))
      (node (ref "IC6") (pin "8") (pinfunction "VCC_8") (pintype "power_in"))
      (node (ref "IC7") (pin "8") (pinfunction "VCC_8") (pintype "bidirectional"))
      (node (ref "IC8") (pin "4") (pinfunction "VDD_4") (pintype "bidirectional"))
      (node (ref "R1") (pin "2") (pinfunction "2_2") (pintype "passive"))
      (node (ref "R11") (pin "1") (pinfunction "1_1") (pintype "passive"))
      (node (ref "R12") (pin "2") (pinfunction "2_2") (pintype "passive"))
      (node (ref "R13") (pin "2") (pinfunction "2_2") (pintype "passive"))
      (node (ref "R2") (pin "2") (pinfunction "2_2") (pintype "passive"))
      (node (ref "RJ11_1") (pin "P$1") (pinfunction "1_P$1") (pintype "bidirectional"))
      (node (ref "RJ11_2") (pin "P$1") (pinfunction "1_P$1") (pintype "bidirectional"))
      (node (ref "U$1") (pin "3.3V") (pinfunction "3.3V_3.3V") (pintype "bidirectional"))
      (node (ref "U$1") (pin "3V3") (pinfunction "3V3_3V3") (pintype "bidirectional"))
    )
    (net (code "34") (name "VCC_5V") (class "Default")
      (node (ref "C7") (pin "1") (pinfunction "1_1") (pintype "passive"))
      (node (ref "EX1") (pin "3") (pinfunction "3_3") (pintype "bidirectional"))
      (node (ref "EX2") (pin "3") (pinfunction "3_3") (pintype "bidirectional"))
      (node (ref "EX3") (pin "3") (pinfunction "3_3") (pintype "bidirectional"))
      (node (ref "IC3") (pin "3") (pinfunction "INPUT_3") (pintype "bidirectional"))
      (node (ref "U$1") (pin "5V") (pinfunction "5V_5V") (pintype "bidirectional"))
      (node (ref "U$2") (pin "OUT+") (pinfunction "OUT+_OUT+") (pintype "bidirectional"))
    )
    (net (code "35") (name "VCC_12V") (class "Default")
      (node (ref "IC6") (pin "3") (pinfunction "IP-_3") (pintype "passive"))
      (node (ref "IC6") (pin "4") (pinfunction "IP-1_4") (pintype "passive"))
      (node (ref "J1") (pin "2") (pinfunction "2_2") (pintype "passive"))
      (node (ref "R9") (pin "1") (pinfunction "1_1") (pintype "passive"))
      (node (ref "U$2") (pin "IN+") (pinfunction "IN+_IN+") (pintype "bidirectional"))
    )
    (net (code "36") (name "VCC_BBANK") (class "Default")
      (node (ref "BBANK") (pin "1") (pinfunction "1_1") (pintype "bidirectional"))
      (node (ref "R5") (pin "1") (pinfunction "1_1") (pintype "passive"))
    )
    (net (code "37") (name "VCC_PV") (class "Default")
      (node (ref "R7") (pin "1") (pinfunction "1_1") (pintype "passive"))
      (node (ref "VPV") (pin "1") (pinfunction "1_1") (pintype "bidirectional"))
    )
    (net (code "38") (name "unconnected-(IC1-NC-Pad4)") (class "Default")
      (node (ref "IC1") (pin "4") (pinfunction "NC_4") (pintype "no_connect"))
    )
    (net (code "39") (name "unconnected-(IC5-AIN2-Pad6)") (class "Default")
      (node (ref "IC5") (pin "6") (pinfunction "AIN2_6") (pintype "bidirectional"))
    )
    (net (code "40") (name "unconnected-(IC5-AIN3-Pad7)") (class "Default")
      (node (ref "IC5") (pin "7") (pinfunction "AIN3_7") (pintype "bidirectional"))
    )
    (net (code "41") (name "unconnected-(IC5-ALERT{slash}RDY-Pad2)") (class "Default")
      (node (ref "IC5") (pin "2") (pinfunction "ALERT/RDY_2") (pintype "bidirectional"))
    )
    (net (code "42") (name "unconnected-(IC8-NC_1-Pad1)") (class "Default")
      (node (ref "IC8") (pin "1") (pinfunction "NC_1_1") (pintype "bidirectional"))
    )
    (net (code "43") (name "unconnected-(IC8-NC_2-Pad5)") (class "Default")
      (node (ref "IC8") (pin "5") (pinfunction "NC_2_5") (pintype "bidirectional"))
    )
    (net (code "44") (name "unconnected-(U$1-Pad2)") (class "Default")
      (node (ref "U$1") (pin "2") (pinfunction "2_2") (pintype "bidirectional"))
    )
    (net (code "45") (name "unconnected-(U$1-PadLORA1)") (class "Default")
      (node (ref "U$1") (pin "LORA1") (pinfunction "LORA1_LORA1") (pintype "bidirectional"))
    )
    (net (code "46") (name "unconnected-(U$1-PadLORA2)") (class "Default")
      (node (ref "U$1") (pin "LORA2") (pinfunction "LORA2_LORA2") (pintype "bidirectional"))
    )
    (net (code "47") (name "~{RXEN}") (class "Default")
      (node (ref "IC7") (pin "2") (pinfunction "~{RE}_2") (pintype "bidirectional"))
      (node (ref "R12") (pin "1") (pinfunction "1_1") (pintype "passive"))
      (node (ref "U$1") (pin "23") (pinfunction "23_23") (pintype "bidirectional"))
    )
  )
)
